# EaglesPU50.net
KiCad netlist of a schematic drawn in Altium Designer
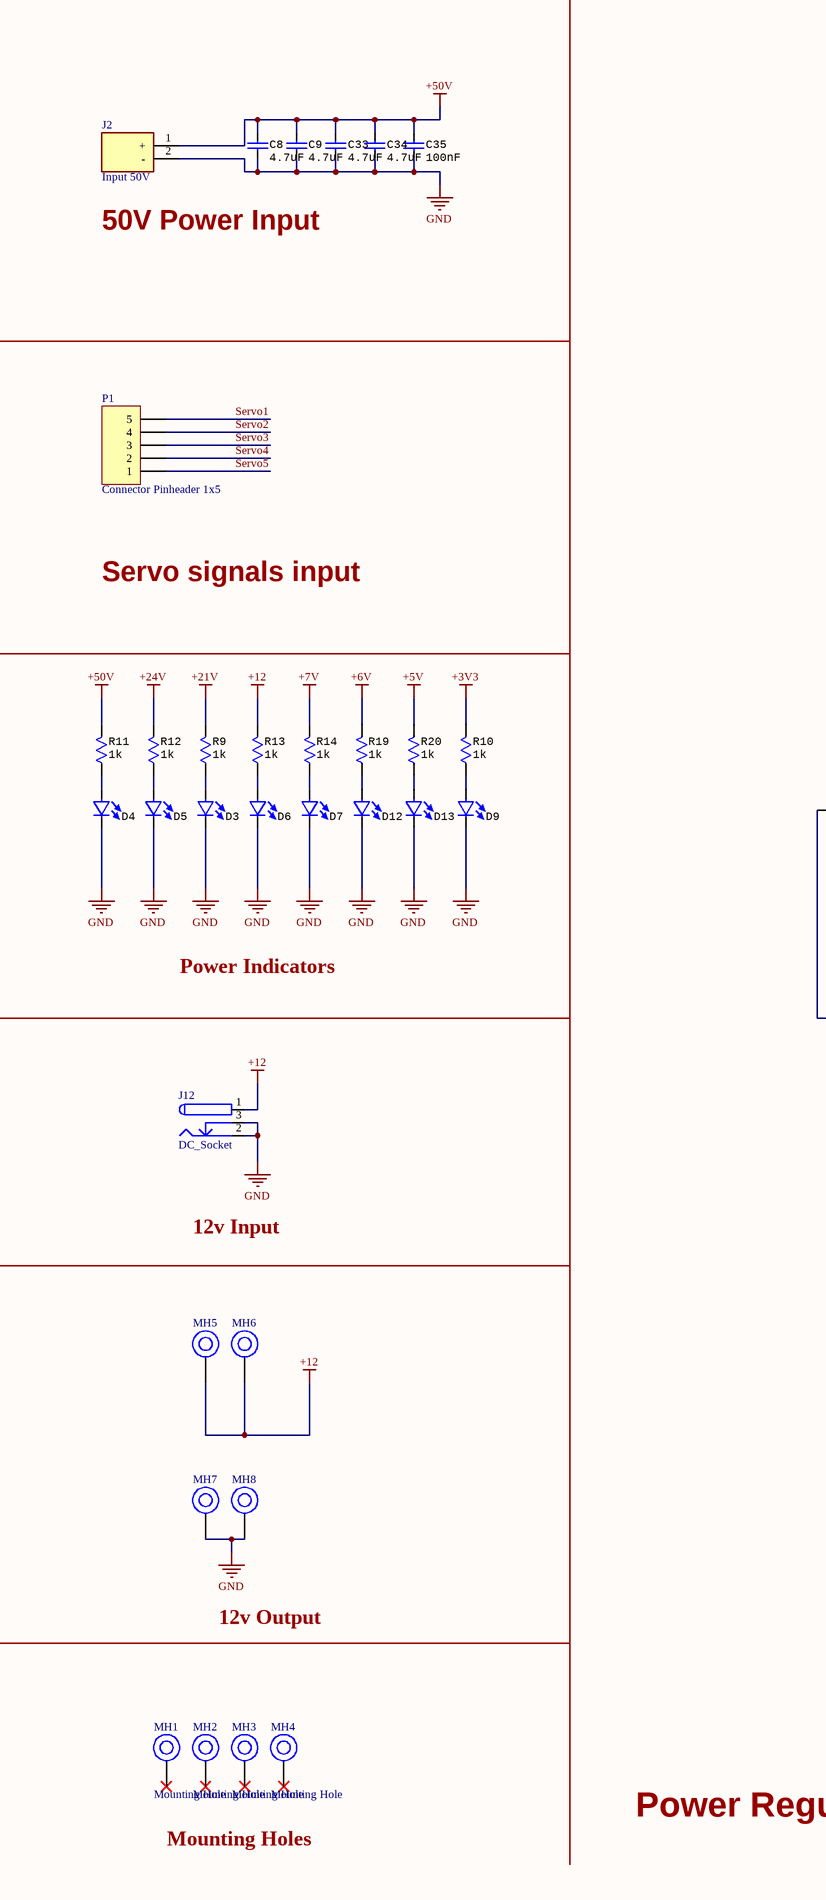
[diagram p0: EaglesPU50.SchDoc, left]
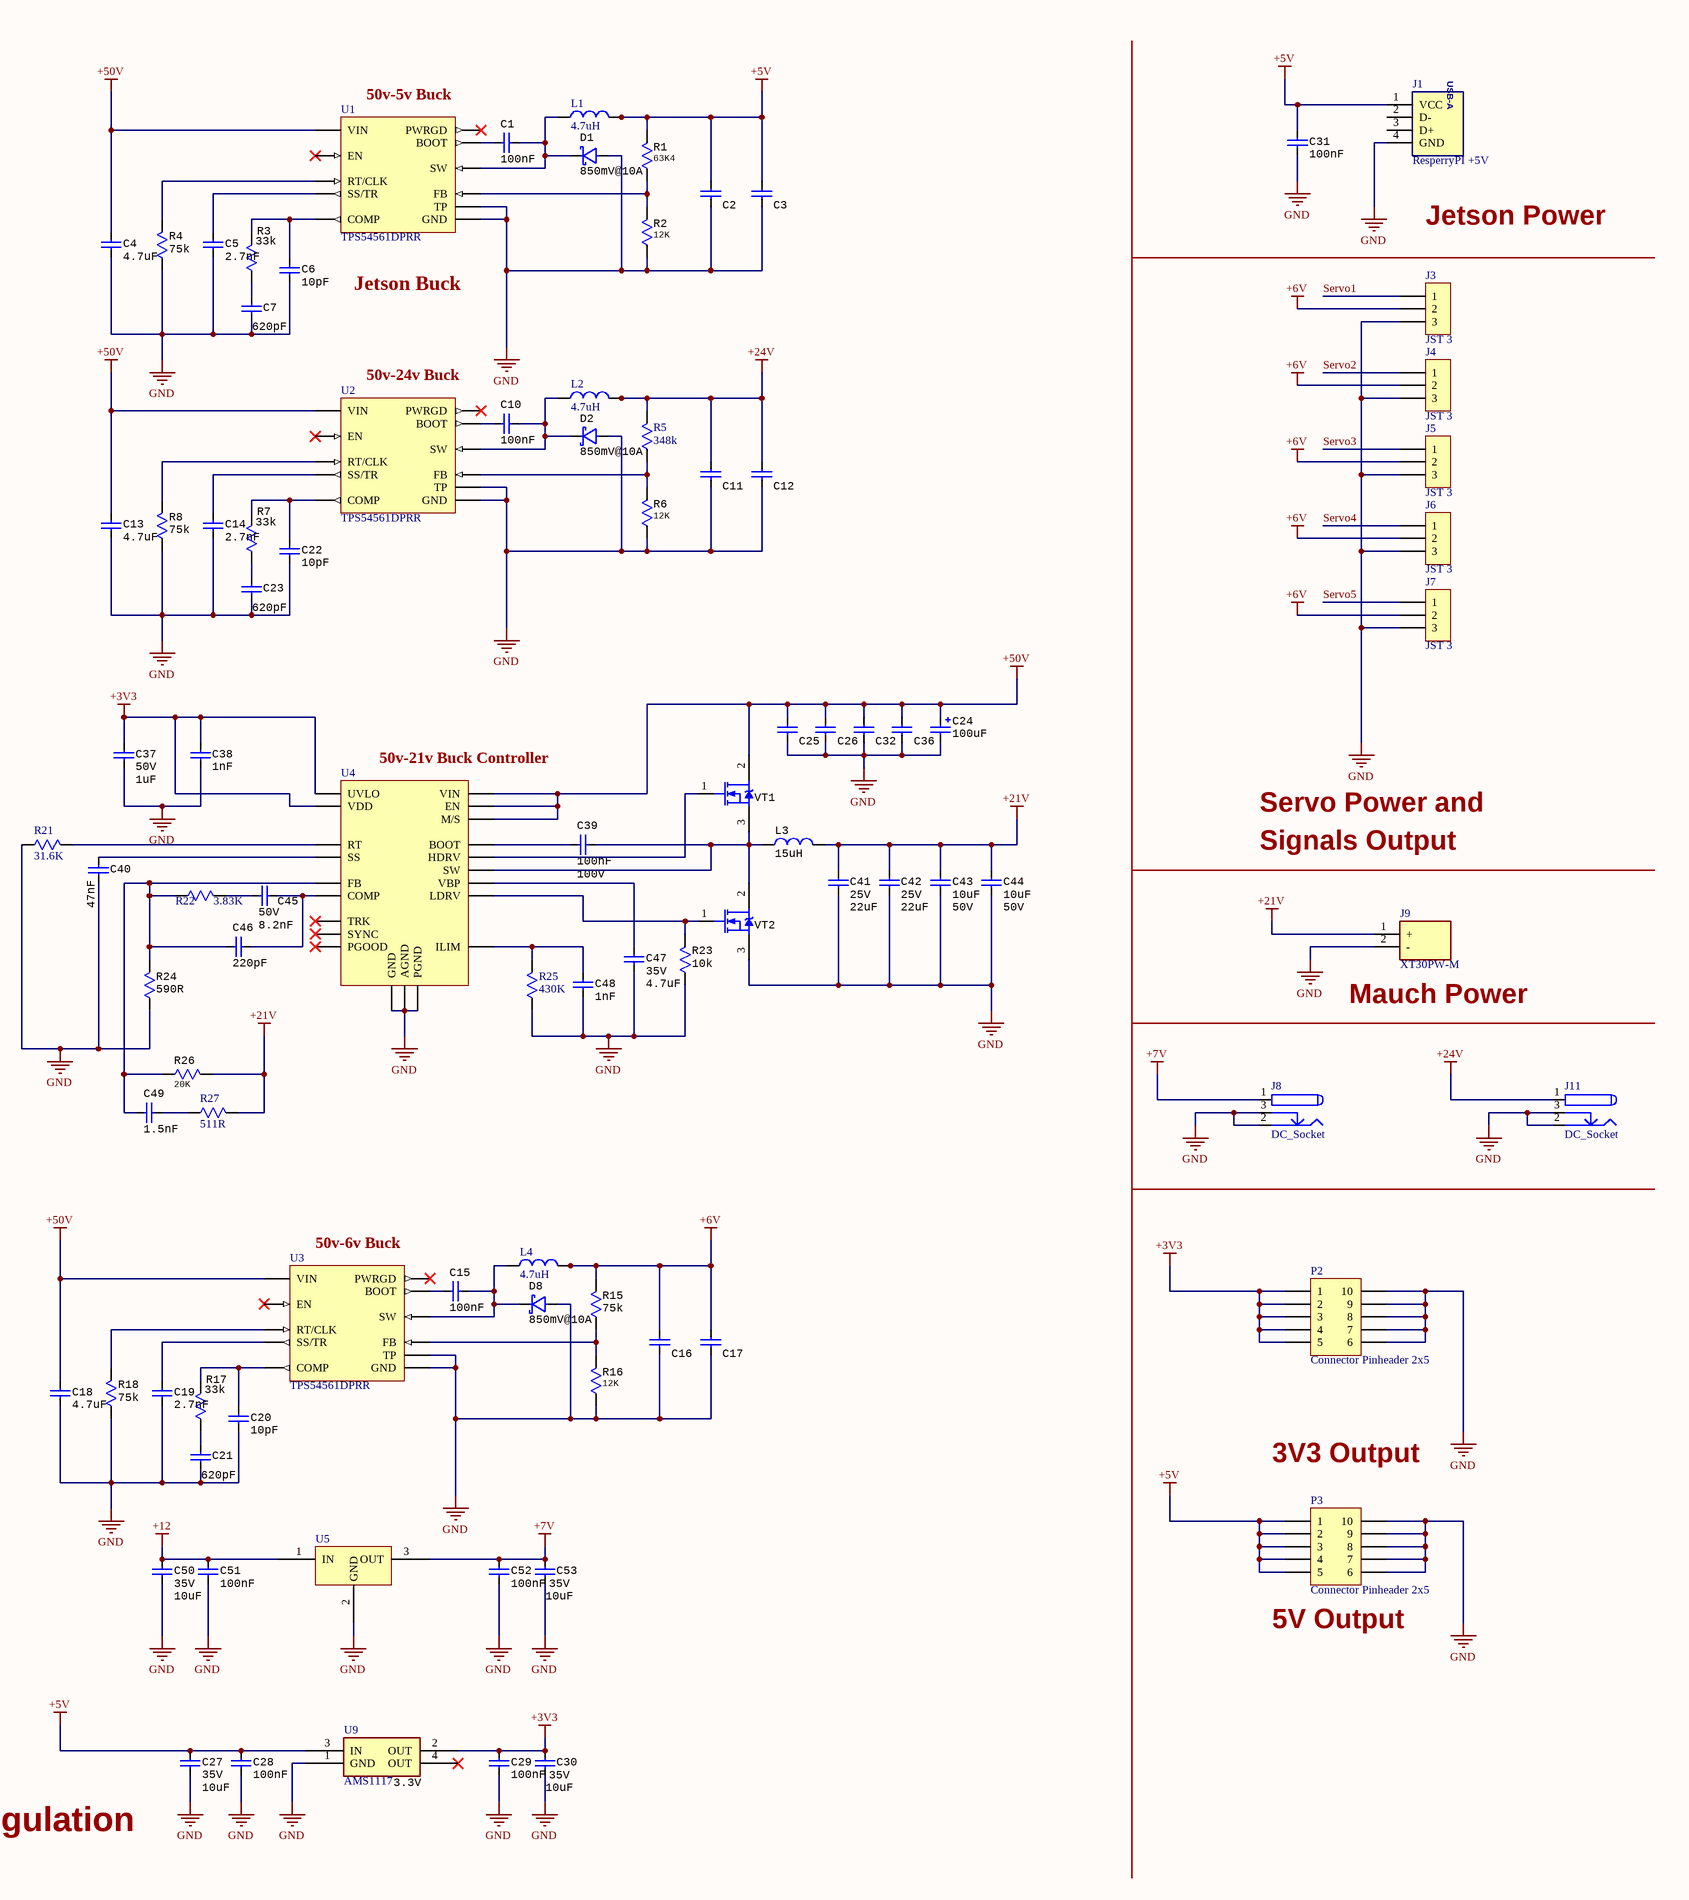
[diagram p1: EaglesPU50.SchDoc, right]

(export (version "E")
  (design (tool "Eeschema 10.0.6"))
  (components
    (comp (ref "C1")
      (value "100nF")
      (footprint "CAP Ceramic SMD 0603")
      (description "0603 0.1 uF 100 V ±10% Tolerance X7R Multilayer Ceramic Capacitor")
      (fields
        (field (name "MANUFACTURER") "Yageo")
        (field (name "MANUFACTURER PART NUMBER") "CC0603KRX7R0BB104")
      )
      (libsource (lib "capacitor") (part "CAP 0603 100nF 100V"))
    )
    (comp (ref "C2")
      (value "~")
      (footprint "CAP Ceramic SMD 1206")
      (description "10V 22uF X7R ±10% 1206 Multilayer Ceramic Capacitors MLCC - SMD/SMT ROHS")
      (fields
        (field (name "MANUFACTURER") "Samsung")
        (field (name "MANUFACTURER PART NUMBER") "GRM31CR61A476ME15L")
      )
      (libsource (lib "capacitor") (part "CAP 1206 47uF 10V X5R"))
    )
    (comp (ref "C3")
      (value "~")
      (footprint "CAP Ceramic SMD 1206")
      (description "10V 22uF X7R ±10% 1206 Multilayer Ceramic Capacitors MLCC - SMD/SMT ROHS")
      (fields
        (field (name "MANUFACTURER") "Samsung")
        (field (name "MANUFACTURER PART NUMBER") "GRM31CR61A476ME15L")
      )
      (libsource (lib "capacitor") (part "CAP 1206 47uF 10V X5R"))
    )
    (comp (ref "C4")
      (value "4.7uF")
      (footprint "CAP Ceramic SMD 1206")
      (description "Cap Ceramic 4.7uF 100V X7S 10% SMD 1206 125°C Emboss T/R")
      (fields
        (field (name "MANUFACTURER PART NUMBER") "GRM31CC72A475KE11L")
        (field (name "MANUFACTURER") "Murata")
      )
      (libsource (lib "Passive") (part "CAP 1206 4.7uF 100V"))
    )
    (comp (ref "C5")
      (value "2.7nF")
      (footprint "CAP Ceramic SMD 0603")
      (description "0603 2.7 nF 50 V ±10 % Tolerance X7R SMT Multilayer Ceramic Capacitor")
      (fields
        (field (name "MANUFACTURER") "Yageo")
        (field (name "MANUFACTURER PART NUMBER") "CC0603KRX7R9BB272")
      )
      (libsource (lib "Passive") (part "CAP 0603 2.7nF 50V"))
    )
    (comp (ref "C6")
      (value "10pF")
      (footprint "CAP Ceramic SMD 0603")
      (description "Surface Mount Ceramic Multilayer Capacitor 10pF 5% C0G 50V 0603 Paper T/R")
      (fields
        (field (name "MANUFACTURER") "Yageo")
        (field (name "MANUFACTURER PART NUMBER") "CC0603JRNPO9BN100")
      )
      (libsource (lib "Passive") (part "CAP 0603 10pF 50V"))
    )
    (comp (ref "C7")
      (value "620pF")
      (footprint "CAP Ceramic SMD 0603")
      (description "Surface Mount Ceramic Multilayer Capacitor 620pF 5% C0G 50V 0603 Paper T/R")
      (fields
        (field (name "MANUFACTURER") "Yageo")
        (field (name "MANUFACTURER PART NUMBER") "CC0603JRNPO9BN621")
      )
      (libsource (lib "Passive") (part "CAP 0603 620pF 50V"))
    )
    (comp (ref "C8")
      (value "4.7uF")
      (footprint "CAP Ceramic SMD 1206")
      (description "Cap Ceramic 4.7uF 100V X7S 10% SMD 1206 125°C Emboss T/R")
      (fields
        (field (name "MANUFACTURER PART NUMBER") "GRM31CC72A475KE11L")
        (field (name "MANUFACTURER") "Murata")
      )
      (libsource (lib "Passive") (part "CAP 1206 4.7uF 100V"))
    )
    (comp (ref "C9")
      (value "4.7uF")
      (footprint "CAP Ceramic SMD 1206")
      (description "Cap Ceramic 4.7uF 100V X7S 10% SMD 1206 125°C Emboss T/R")
      (fields
        (field (name "MANUFACTURER PART NUMBER") "GRM31CC72A475KE11L")
        (field (name "MANUFACTURER") "Murata")
      )
      (libsource (lib "Passive") (part "CAP 1206 4.7uF 100V"))
    )
    (comp (ref "C10")
      (value "100nF")
      (footprint "CAP Ceramic SMD 0603")
      (description "0603 0.1 uF 100 V ±10% Tolerance X7R Multilayer Ceramic Capacitor")
      (fields
        (field (name "MANUFACTURER") "Yageo")
        (field (name "MANUFACTURER PART NUMBER") "CC0603KRX7R0BB104")
      )
      (libsource (lib "capacitor") (part "CAP 0603 100nF 100V"))
    )
    (comp (ref "C11")
      (value "~")
      (footprint "CAP Ceramic SMD 1206")
      (description "10V 22uF X7R ±10% 1206 Multilayer Ceramic Capacitors MLCC - SMD/SMT ROHS")
      (fields
        (field (name "MANUFACTURER") "Samsung")
        (field (name "MANUFACTURER PART NUMBER") "GRM31CR61A476ME15L")
      )
      (libsource (lib "capacitor") (part "CAP 1206 47uF 10V X5R"))
    )
    (comp (ref "C12")
      (value "~")
      (footprint "CAP Ceramic SMD 1206")
      (description "10V 22uF X7R ±10% 1206 Multilayer Ceramic Capacitors MLCC - SMD/SMT ROHS")
      (fields
        (field (name "MANUFACTURER") "Samsung")
        (field (name "MANUFACTURER PART NUMBER") "GRM31CR61A476ME15L")
      )
      (libsource (lib "capacitor") (part "CAP 1206 47uF 10V X5R"))
    )
    (comp (ref "C13")
      (value "4.7uF")
      (footprint "CAP Ceramic SMD 1206")
      (description "Cap Ceramic 4.7uF 100V X7S 10% SMD 1206 125°C Emboss T/R")
      (fields
        (field (name "MANUFACTURER PART NUMBER") "GRM31CC72A475KE11L")
        (field (name "MANUFACTURER") "Murata")
      )
      (libsource (lib "Passive") (part "CAP 1206 4.7uF 100V"))
    )
    (comp (ref "C14")
      (value "2.7nF")
      (footprint "CAP Ceramic SMD 0603")
      (description "0603 2.7 nF 50 V ±10 % Tolerance X7R SMT Multilayer Ceramic Capacitor")
      (fields
        (field (name "MANUFACTURER") "Yageo")
        (field (name "MANUFACTURER PART NUMBER") "CC0603KRX7R9BB272")
      )
      (libsource (lib "Passive") (part "CAP 0603 2.7nF 50V"))
    )
    (comp (ref "C15")
      (value "100nF")
      (footprint "CAP Ceramic SMD 0603")
      (description "0603 0.1 uF 100 V ±10% Tolerance X7R Multilayer Ceramic Capacitor")
      (fields
        (field (name "MANUFACTURER") "Yageo")
        (field (name "MANUFACTURER PART NUMBER") "CC0603KRX7R0BB104")
      )
      (libsource (lib "capacitor") (part "CAP 0603 100nF 100V"))
    )
    (comp (ref "C16")
      (value "~")
      (footprint "CAP Ceramic SMD 1206")
      (description "10V 22uF X7R ±10% 1206 Multilayer Ceramic Capacitors MLCC - SMD/SMT ROHS")
      (fields
        (field (name "MANUFACTURER") "Samsung")
        (field (name "MANUFACTURER PART NUMBER") "GRM31CR61A476ME15L")
      )
      (libsource (lib "capacitor") (part "CAP 1206 47uF 10V X5R"))
    )
    (comp (ref "C17")
      (value "~")
      (footprint "CAP Ceramic SMD 1206")
      (description "10V 22uF X7R ±10% 1206 Multilayer Ceramic Capacitors MLCC - SMD/SMT ROHS")
      (fields
        (field (name "MANUFACTURER") "Samsung")
        (field (name "MANUFACTURER PART NUMBER") "GRM31CR61A476ME15L")
      )
      (libsource (lib "capacitor") (part "CAP 1206 47uF 10V X5R"))
    )
    (comp (ref "C18")
      (value "4.7uF")
      (footprint "CAP Ceramic SMD 1206")
      (description "Cap Ceramic 4.7uF 100V X7S 10% SMD 1206 125°C Emboss T/R")
      (fields
        (field (name "MANUFACTURER PART NUMBER") "GRM31CC72A475KE11L")
        (field (name "MANUFACTURER") "Murata")
      )
      (libsource (lib "Passive") (part "CAP 1206 4.7uF 100V"))
    )
    (comp (ref "C19")
      (value "2.7nF")
      (footprint "CAP Ceramic SMD 0603")
      (description "0603 2.7 nF 50 V ±10 % Tolerance X7R SMT Multilayer Ceramic Capacitor")
      (fields
        (field (name "MANUFACTURER") "Yageo")
        (field (name "MANUFACTURER PART NUMBER") "CC0603KRX7R9BB272")
      )
      (libsource (lib "Passive") (part "CAP 0603 2.7nF 50V"))
    )
    (comp (ref "C20")
      (value "10pF")
      (footprint "CAP Ceramic SMD 0603")
      (description "Surface Mount Ceramic Multilayer Capacitor 10pF 5% C0G 50V 0603 Paper T/R")
      (fields
        (field (name "MANUFACTURER") "Yageo")
        (field (name "MANUFACTURER PART NUMBER") "CC0603JRNPO9BN100")
      )
      (libsource (lib "Passive") (part "CAP 0603 10pF 50V"))
    )
    (comp (ref "C21")
      (value "620pF")
      (footprint "CAP Ceramic SMD 0603")
      (description "Surface Mount Ceramic Multilayer Capacitor 620pF 5% C0G 50V 0603 Paper T/R")
      (fields
        (field (name "MANUFACTURER") "Yageo")
        (field (name "MANUFACTURER PART NUMBER") "CC0603JRNPO9BN621")
      )
      (libsource (lib "Passive") (part "CAP 0603 620pF 50V"))
    )
    (comp (ref "C22")
      (value "10pF")
      (footprint "CAP Ceramic SMD 0603")
      (description "Surface Mount Ceramic Multilayer Capacitor 10pF 5% C0G 50V 0603 Paper T/R")
      (fields
        (field (name "MANUFACTURER") "Yageo")
        (field (name "MANUFACTURER PART NUMBER") "CC0603JRNPO9BN100")
      )
      (libsource (lib "Passive") (part "CAP 0603 10pF 50V"))
    )
    (comp (ref "C23")
      (value "620pF")
      (footprint "CAP Ceramic SMD 0603")
      (description "Surface Mount Ceramic Multilayer Capacitor 620pF 5% C0G 50V 0603 Paper T/R")
      (fields
        (field (name "MANUFACTURER") "Yageo")
        (field (name "MANUFACTURER PART NUMBER") "CC0603JRNPO9BN621")
      )
      (libsource (lib "Passive") (part "CAP 0603 620pF 50V"))
    )
    (comp (ref "C24")
      (value "100uF")
      (footprint "CAP Electrolytic SMD G_10X10.3X10.2(CPOL-EU153CLV-1010)")
      (fields (field (name "MANUFACTURER") "ROQANG") (field (name "MANUFACTURER PART NUMBER") "RT1J101M1010"))
      (libsource (lib "Passive") (part "CAP ELEC 100uF 68V"))
    )
    (comp (ref "C25")
      (value "2.2uF")
      (footprint "CAP Ceramic SMD 1206")
      (description "100V 2.2uF X7R ±10% 1206 Multilayer Ceramic Capacitors MLCC - SMD/SMT ROHS")
      (fields
        (field (name "MANUFACTURER") "Yageo")
        (field (name "MANUFACTURER PART NUMBER") "CC1206KKX7R0BB225")
      )
      (libsource (lib "Passive") (part "CAP 1206 2.2uF 100V"))
    )
    (comp (ref "C26")
      (value "2.2uF")
      (footprint "CAP Ceramic SMD 1206")
      (description "100V 2.2uF X7R ±10% 1206 Multilayer Ceramic Capacitors MLCC - SMD/SMT ROHS")
      (fields
        (field (name "MANUFACTURER") "Yageo")
        (field (name "MANUFACTURER PART NUMBER") "CC1206KKX7R0BB225")
      )
      (libsource (lib "Passive") (part "CAP 1206 2.2uF 100V"))
    )
    (comp (ref "C27")
      (value "10uF")
      (footprint "CAP Ceramic SMD 0603")
      (description "Cap Ceramic 10uF 35V X5R 20% Pad SMD 0603 85C T/R")
      (fields
        (field (name "MANUFACTURER") "Murata")
        (field (name "MANUFACTURER PART NUMBER") "GRM188R6YA106MA73D")
        (field (name "VOLTAGE") "35V")
      )
      (libsource (lib "Passive") (part "CAP 0603 10uF 35V"))
    )
    (comp (ref "C28")
      (value "100nF")
      (footprint "CAP Ceramic SMD 0603")
      (description "0603 0.1 uF 100 V ±10% Tolerance X7R Multilayer Ceramic Capacitor")
      (fields
        (field (name "MANUFACTURER") "Yageo")
        (field (name "MANUFACTURER PART NUMBER") "AC0603KRX7R0BB104")
      )
      (libsource (lib "capacitor") (part "CAP 0603 100nF 100V"))
    )
    (comp (ref "C29")
      (value "100nF")
      (footprint "CAP Ceramic SMD 0603")
      (description "0603 0.1 uF 100 V ±10% Tolerance X7R Multilayer Ceramic Capacitor")
      (fields
        (field (name "MANUFACTURER") "Yageo")
        (field (name "MANUFACTURER PART NUMBER") "AC0603KRX7R0BB104")
      )
      (libsource (lib "capacitor") (part "CAP 0603 100nF 100V"))
    )
    (comp (ref "C30")
      (value "10uF")
      (footprint "CAP Ceramic SMD 0603")
      (description "Cap Ceramic 10uF 35V X5R 20% Pad SMD 0603 85C T/R")
      (fields
        (field (name "MANUFACTURER") "Murata")
        (field (name "MANUFACTURER PART NUMBER") "GRM188R6YA106MA73D")
        (field (name "VOLTAGE") "35V")
      )
      (libsource (lib "Passive") (part "CAP 0603 10uF 35V"))
    )
    (comp (ref "C31")
      (value "100nF")
      (footprint "CAP Ceramic SMD 0603")
      (description "0603 0.1 uF 100 V ±10% Tolerance X7R Multilayer Ceramic Capacitor")
      (fields
        (field (name "MANUFACTURER") "Yageo")
        (field (name "MANUFACTURER PART NUMBER") "CC0603KRX7R0BB104")
      )
      (libsource (lib "capacitor") (part "CAP 0603 100nF 100V"))
    )
    (comp (ref "C32")
      (value "2.2uF")
      (footprint "CAP Ceramic SMD 1206")
      (description "100V 2.2uF X7R ±10% 1206 Multilayer Ceramic Capacitors MLCC - SMD/SMT ROHS")
      (fields
        (field (name "MANUFACTURER") "Yageo")
        (field (name "MANUFACTURER PART NUMBER") "CC1206KKX7R0BB225")
      )
      (libsource (lib "Passive") (part "CAP 1206 2.2uF 100V"))
    )
    (comp (ref "C33")
      (value "4.7uF")
      (footprint "CAP Ceramic SMD 1206")
      (description "Cap Ceramic 4.7uF 100V X7S 10% SMD 1206 125°C Emboss T/R")
      (fields
        (field (name "MANUFACTURER PART NUMBER") "GRM31CC72A475KE11L")
        (field (name "MANUFACTURER") "Murata")
      )
      (libsource (lib "Passive") (part "CAP 1206 4.7uF 100V"))
    )
    (comp (ref "C34")
      (value "4.7uF")
      (footprint "CAP Ceramic SMD 1206")
      (description "Cap Ceramic 4.7uF 100V X7S 10% SMD 1206 125°C Emboss T/R")
      (fields
        (field (name "MANUFACTURER PART NUMBER") "GRM31CC72A475KE11L")
        (field (name "MANUFACTURER") "Murata")
      )
      (libsource (lib "Passive") (part "CAP 1206 4.7uF 100V"))
    )
    (comp (ref "C35")
      (value "100nF")
      (footprint "CAP Ceramic SMD 0603")
      (description "0603 0.1 uF 100 V ±10% Tolerance X7R Multilayer Ceramic Capacitor")
      (fields
        (field (name "MANUFACTURER") "Yageo")
        (field (name "MANUFACTURER PART NUMBER") "CC0603KRX7R0BB104")
      )
      (libsource (lib "capacitor") (part "CAP 0603 100nF 100V"))
    )
    (comp (ref "C36")
      (value "2.2uF")
      (footprint "CAP Ceramic SMD 1206")
      (description "100V 2.2uF X7R ±10% 1206 Multilayer Ceramic Capacitors MLCC - SMD/SMT ROHS")
      (fields
        (field (name "MANUFACTURER") "Yageo")
        (field (name "MANUFACTURER PART NUMBER") "CC1206KKX7R0BB225")
      )
      (libsource (lib "Passive") (part "CAP 1206 2.2uF 100V"))
    )
    (comp (ref "C37")
      (value "1uF")
      (footprint "CAP Ceramic SMD 0603")
      (description "50V 1uF X7R ±10% 0603 Multilayer Ceramic Capacitors MLCC - SMD/SMT ROHS")
      (fields
        (field (name "MANUFACTURER") "YAGEO")
        (field (name "MANUFACTURER PART NUMBER") "CC0603KRX7R9BB105")
        (field (name "VOLTAGE") "50V")
      )
      (libsource (lib "Passive") (part "CAP 0603 1uF 50V X7R 10%"))
    )
    (comp (ref "C38")
      (value "1nF")
      (footprint "CAP Ceramic SMD 0603")
      (description "CAP CER 1100PF 50V C0G/NP0 0603")
      (fields
        (field (name "MANUFACTURER") "YAGEO")
        (field (name "MANUFACTURER PART NUMBER") "CC0603KRX7R9BB102")
      )
      (libsource (lib "Passive") (part "CAP 0603 1nF 50V"))
    )
    (comp (ref "C39")
      (value "100nF")
      (footprint "CAP Ceramic SMD 0603")
      (description "100V 100nF X7R ±10% 0603 Multilayer Ceramic Capacitors MLCC - SMD/SMT ROHS")
      (fields
        (field (name "MANUFACTURER") "Yageo")
        (field (name "MANUFACTURER PART NUMBER") "CC0603KRX7R0BB104")
        (field (name "VOLTAGE") "100V")
      )
      (libsource (lib "Passive") (part "CAP 0603 100nF 100V X7R 10%"))
    )
    (comp (ref "C40")
      (value "47nF")
      (footprint "CAP Ceramic SMD 0603")
      (description "50V 47nF X7R ±10% 0603 Multilayer Ceramic Capacitors MLCC - SMD/SMT ROHS")
      (fields
        (field (name "MANUFACTURER") "Yageo")
        (field (name "MANUFACTURER PART NUMBER") "CC0603KRX7R9BB473")
      )
      (libsource (lib "Passive") (part "CAP 0603 47nF 50V"))
    )
    (comp (ref "C41")
      (value "22uF")
      (footprint "CAP Ceramic SMD 0805")
      (description "25V 22uF X5R ±20% 0805 Multilayer Ceramic Capacitors MLCC")
      (fields
        (field (name "MANUFACTURER") "YAGEO")
        (field (name "MANUFACTURER PART NUMBER") "CC0805MKX5R8BB226")
        (field (name "VOLTAGE") "25V")
      )
      (libsource (lib "Passive") (part "CAP 0805 22uF 25V"))
    )
    (comp (ref "C42")
      (value "22uF")
      (footprint "CAP Ceramic SMD 0805")
      (description "25V 22uF X5R ±20% 0805 Multilayer Ceramic Capacitors MLCC")
      (fields
        (field (name "MANUFACTURER") "YAGEO")
        (field (name "MANUFACTURER PART NUMBER") "CC0805MKX5R8BB226")
        (field (name "VOLTAGE") "25V")
      )
      (libsource (lib "Passive") (part "CAP 0805 22uF 25V"))
    )
    (comp (ref "C43")
      (value "10uF")
      (footprint "CAP Ceramic SMD 1206")
      (description "50V 10uF X5R ±10% 1206 Multilayer Ceramic Capacitors MLCC - SMD/SMT ROHS")
      (fields
        (field (name "MANUFACTURER") "Samsung")
        (field (name "MANUFACTURER PART NUMBER") "CL31A106KBHNNNE")
        (field (name "VOLTAGE") "50V")
      )
      (libsource (lib "Passive") (part "CAP 1206 10uF 50V X5R 10%"))
    )
    (comp (ref "C44")
      (value "10uF")
      (footprint "CAP Ceramic SMD 1206")
      (description "50V 10uF X5R ±10% 1206 Multilayer Ceramic Capacitors MLCC - SMD/SMT ROHS")
      (fields
        (field (name "MANUFACTURER") "Samsung")
        (field (name "MANUFACTURER PART NUMBER") "CL31A106KBHNNNE")
        (field (name "VOLTAGE") "50V")
      )
      (libsource (lib "Passive") (part "CAP 1206 10uF 50V X5R 10%"))
    )
    (comp (ref "C45")
      (value "8.2nF")
      (footprint "CAP Ceramic SMD 0603")
      (description "50V 8.2nF X7R ±10% 0603 Multilayer Ceramic Capacitors MLCC - SMD/SMT ROHS")
      (fields
        (field (name "MANUFACTURER") "YAGEO")
        (field (name "MANUFACTURER PART NUMBER") "CC0603KRX7R9BB822")
        (field (name "VOLTAGE") "50V")
        (field (name "CAPACITANCE") "8.2nF")
      )
      (libsource (lib "Passive") (part "CAP 0603 8.2nF 50V"))
    )
    (comp (ref "C46")
      (value "220pF")
      (footprint "CAP Ceramic SMD 0603")
      (description "50V 220pF X7R ±10% 0603 Multilayer Ceramic Capacitors MLCC - SMD/SMT ROHS")
      (fields
        (field (name "MANUFACTURER") "Yageo")
        (field (name "MANUFACTURER PART NUMBER") "CC0603KRX7R9BB221")
      )
      (libsource (lib "Passive") (part "CAP 0603 220pF 50V"))
    )
    (comp (ref "C47")
      (value "4.7uF")
      (footprint "CAP Ceramic SMD 0603")
      (description "25V 4.7uF X5R ±10% 0603 Multilayer Ceramic Capacitors MLCC - SMD/SMT ROHS")
      (fields
        (field (name "MANUFACTURER") "Samsung Electro-Mechanics")
        (field (name "MANUFACTURER PART NUMBER") "CL10A475KA8NQNC")
        (field (name "VOLTAGE") "35V")
      )
      (libsource (lib "Passive") (part "CAP 0603 4.7uF 25V X5R 10%"))
    )
    (comp (ref "C48")
      (value "1nF")
      (footprint "CAP Ceramic SMD 0603")
      (description "CAP CER 1100PF 50V C0G/NP0 0603")
      (fields
        (field (name "MANUFACTURER") "YAGEO")
        (field (name "MANUFACTURER PART NUMBER") "CC0603KRX7R9BB102")
      )
      (libsource (lib "Passive") (part "CAP 0603 1nF 50V"))
    )
    (comp (ref "C49")
      (value "1.5nF")
      (footprint "CAP Ceramic SMD 0603")
      (description "50V 1.5nF X7R ±10% 0603 Multilayer Ceramic Capacitors MLCC - SMD/SMT ROHS")
      (fields
        (field (name "MANUFACTURER") "Yageo")
        (field (name "MANUFACTURER PART NUMBER") "CC0603KRX7R9BB152")
      )
      (libsource (lib "Passive") (part "CAP 0603 1.5nF 50V"))
    )
    (comp (ref "C50")
      (value "10uF")
      (footprint "CAP Ceramic SMD 0603")
      (description "Cap Ceramic 10uF 35V X5R 20% Pad SMD 0603 85C T/R")
      (fields
        (field (name "MANUFACTURER") "Murata")
        (field (name "MANUFACTURER PART NUMBER") "GRM188R6YA106MA73D")
        (field (name "VOLTAGE") "35V")
      )
      (libsource (lib "Passive") (part "CAP 0603 10uF 35V"))
    )
    (comp (ref "C51")
      (value "100nF")
      (footprint "CAP Ceramic SMD 0603")
      (description "0603 0.1 uF 100 V ±10% Tolerance X7R Multilayer Ceramic Capacitor")
      (fields
        (field (name "MANUFACTURER") "Yageo")
        (field (name "MANUFACTURER PART NUMBER") "AC0603KRX7R0BB104")
      )
      (libsource (lib "capacitor") (part "CAP 0603 100nF 100V"))
    )
    (comp (ref "C52")
      (value "100nF")
      (footprint "CAP Ceramic SMD 0603")
      (description "0603 0.1 uF 100 V ±10% Tolerance X7R Multilayer Ceramic Capacitor")
      (fields
        (field (name "MANUFACTURER") "Yageo")
        (field (name "MANUFACTURER PART NUMBER") "AC0603KRX7R0BB104")
      )
      (libsource (lib "capacitor") (part "CAP 0603 100nF 100V"))
    )
    (comp (ref "C53")
      (value "10uF")
      (footprint "CAP Ceramic SMD 0603")
      (description "Cap Ceramic 10uF 35V X5R 20% Pad SMD 0603 85C T/R")
      (fields
        (field (name "MANUFACTURER") "Murata")
        (field (name "MANUFACTURER PART NUMBER") "GRM188R6YA106MA73D")
        (field (name "VOLTAGE") "35V")
      )
      (libsource (lib "Passive") (part "CAP 0603 10uF 35V"))
    )
    (comp (ref "D1")
      (value "850mV@10A")
      (footprint "TO-277")
      (description "100V 750mV@10A 10A TO-277 Schottky Barrier Diodes (SBD) ROHS")
      (fields
        (field (name "MANUFACTURER") "MDD（Microdiode Electronics）")
        (field (name "MANUFACTURER PART NUMBER") "SB10100L")
      )
      (libsource (lib "Diode") (part "Schottky 100V 750mV@10A"))
    )
    (comp (ref "D2")
      (value "850mV@10A")
      (footprint "TO-277")
      (description "100V 750mV@10A 10A TO-277 Schottky Barrier Diodes (SBD) ROHS")
      (fields
        (field (name "MANUFACTURER") "MDD（Microdiode Electronics）")
        (field (name "MANUFACTURER PART NUMBER") "SB10100L")
      )
      (libsource (lib "Diode") (part "Schottky 100V 750mV@10A"))
    )
    (comp (ref "D3")
      (value "~")
      (footprint "LED SMD 0805G")
      (description "emerald 0805 Light Emitting Diodes (LED) ROHS")
      (fields
        (field (name "MANUFACTURER") "FOSHAN Nationstar Optoelectronics")
        (field (name "MANUFACTURER PART NUMBER") "NCD0805G1")
      )
      (libsource (lib "diode") (part "LED 0805 Emerald"))
    )
    (comp (ref "D4")
      (value "~")
      (footprint "LED SMD 0805G")
      (description "emerald 0805 Light Emitting Diodes (LED) ROHS")
      (fields
        (field (name "MANUFACTURER") "FOSHAN Nationstar Optoelectronics")
        (field (name "MANUFACTURER PART NUMBER") "NCD0805G1")
      )
      (libsource (lib "diode") (part "LED 0805 Emerald"))
    )
    (comp (ref "D5")
      (value "~")
      (footprint "LED SMD 0805G")
      (description "emerald 0805 Light Emitting Diodes (LED) ROHS")
      (fields
        (field (name "MANUFACTURER") "FOSHAN Nationstar Optoelectronics")
        (field (name "MANUFACTURER PART NUMBER") "NCD0805G1")
      )
      (libsource (lib "diode") (part "LED 0805 Emerald"))
    )
    (comp (ref "D6")
      (value "~")
      (footprint "LED SMD 0805G")
      (description "emerald 0805 Light Emitting Diodes (LED) ROHS")
      (fields
        (field (name "MANUFACTURER") "FOSHAN Nationstar Optoelectronics")
        (field (name "MANUFACTURER PART NUMBER") "NCD0805G1")
      )
      (libsource (lib "diode") (part "LED 0805 Emerald"))
    )
    (comp (ref "D7")
      (value "~")
      (footprint "LED SMD 0805G")
      (description "emerald 0805 Light Emitting Diodes (LED) ROHS")
      (fields
        (field (name "MANUFACTURER") "FOSHAN Nationstar Optoelectronics")
        (field (name "MANUFACTURER PART NUMBER") "NCD0805G1")
      )
      (libsource (lib "diode") (part "LED 0805 Emerald"))
    )
    (comp (ref "D8")
      (value "850mV@10A")
      (footprint "TO-277")
      (description "100V 750mV@10A 10A TO-277 Schottky Barrier Diodes (SBD) ROHS")
      (fields
        (field (name "MANUFACTURER") "MDD（Microdiode Electronics）")
        (field (name "MANUFACTURER PART NUMBER") "SB10100L")
      )
      (libsource (lib "Diode") (part "Schottky 100V 750mV@10A"))
    )
    (comp (ref "D9")
      (value "~")
      (footprint "LED SMD 0805G")
      (description "emerald 0805 Light Emitting Diodes (LED) ROHS")
      (fields
        (field (name "MANUFACTURER") "FOSHAN Nationstar Optoelectronics")
        (field (name "MANUFACTURER PART NUMBER") "NCD0805G1")
      )
      (libsource (lib "diode") (part "LED 0805 Emerald"))
    )
    (comp (ref "D12")
      (value "~")
      (footprint "LED SMD 0805G")
      (description "emerald 0805 Light Emitting Diodes (LED) ROHS")
      (fields
        (field (name "MANUFACTURER") "FOSHAN Nationstar Optoelectronics")
        (field (name "MANUFACTURER PART NUMBER") "NCD0805G1")
      )
      (libsource (lib "diode") (part "LED 0805 Emerald"))
    )
    (comp (ref "D13")
      (value "~")
      (footprint "LED SMD 0805G")
      (description "emerald 0805 Light Emitting Diodes (LED) ROHS")
      (fields
        (field (name "MANUFACTURER") "FOSHAN Nationstar Optoelectronics")
        (field (name "MANUFACTURER PART NUMBER") "NCD0805G1")
      )
      (libsource (lib "diode") (part "LED 0805 Emerald"))
    )
    (comp (ref "J1")
      (value "ResperryPI +5V")
      (footprint "USB-A/S_A")
      (libsource (lib "USB connectors") (part "Connector_USB-A"))
    )
    (comp (ref "J2")
      (value "Input 50V")
      (footprint "XT60PW-M")
      (description "Power Connectors ROHS")
      (fields
        (field (name "MANUFACTURER") "Changzhou Amass Elec")
        (field (name "MANUFACTURERPARTNUMBER") "XT60PW-M")
      )
      (libsource (lib "Power connectors") (part "XT60PW-M"))
    )
    (comp (ref "J3")
      (value "JST 3")
      (footprint "VH3.96-3AW")
      (description "MaleHeader 3x1")
      (libsource (lib "Signal connectors") (part "JST 3"))
    )
    (comp (ref "J4")
      (value "JST 3")
      (footprint "VH3.96-3AW")
      (description "MaleHeader 3x1")
      (libsource (lib "Signal connectors") (part "JST 3"))
    )
    (comp (ref "J5")
      (value "JST 3")
      (footprint "VH3.96-3AW")
      (description "MaleHeader 3x1")
      (libsource (lib "Signal connectors") (part "JST 3"))
    )
    (comp (ref "J6")
      (value "JST 3")
      (footprint "VH3.96-3AW")
      (description "MaleHeader 3x1")
      (libsource (lib "Signal connectors") (part "JST 3"))
    )
    (comp (ref "J7")
      (value "JST 3")
      (footprint "VH3.96-3AW")
      (description "MaleHeader 3x1")
      (libsource (lib "Signal connectors") (part "JST 3"))
    )
    (comp (ref "J8")
      (value "DC_Socket")
      (footprint "DC-002")
      (description "CIRCULAR DC POWER CONNECTOR\r\nRated Current: 7.5A\r\nRated Volatage: 20VDC")
      (libsource (lib "Power connectors") (part "DC_Socket"))
    )
    (comp (ref "J9")
      (value "XT30PW-M")
      (footprint "AMASS_XT30PW-F")
      (description "Power Connectors ROHS")
      (fields (field (name "MANUFACTURER") "Changzhou Amass Elec"))
      (libsource (lib "Power connectors") (part "XT30PW-M"))
    )
    (comp (ref "J11")
      (value "DC_Socket")
      (footprint "DC-002")
      (description "CIRCULAR DC POWER CONNECTOR\r\nRated Current: 7.5A\r\nRated Volatage: 20VDC")
      (libsource (lib "Power connectors") (part "DC_Socket"))
    )
    (comp (ref "J12")
      (value "DC_Socket")
      (footprint "DC-002")
      (description "CIRCULAR DC POWER CONNECTOR\r\nRated Current: 7.5A\r\nRated Volatage: 20VDC")
      (libsource (lib "") (part "DC_Socket_1"))
    )
    (comp (ref "L1")
      (value "4.7uH")
      (footprint "XLS1040")
      (description "9A 4.7uH ±20% 17mΩ 15A SMD,11.5x10x3.8mm Power Inductors ROHS")
      (fields
        (field (name "MANUFACTURER") "Cjiang")
        (field (name "MANUFACTURER PART NUMBER") "FXL1040-4R7-M")
      )
      (libsource (lib "Passive") (part "IND 0403 4.7uH 20%"))
    )
    (comp (ref "L2")
      (value "4.7uH")
      (footprint "XLS1040")
      (description "9A 4.7uH ±20% 17mΩ 15A SMD,11.5x10x3.8mm Power Inductors ROHS")
      (fields
        (field (name "MANUFACTURER") "Cjiang")
        (field (name "MANUFACTURER PART NUMBER") "FXL1040-4R7-M")
      )
      (libsource (lib "Passive") (part "IND 0403 4.7uH 20%"))
    )
    (comp (ref "L3")
      (value "15uH")
      (footprint "MDA1365-150M")
      (description "11A 15uH ±20% 13.5A 22mΩ SMD,12.6x13.5mm Inductors (SMD) ROHS")
      (fields
        (field (name "MANUFACTURER") "KOHERelec")
        (field (name "MANUFACTURER PART NUMBER") "MDA1365-150M")
      )
      (libsource (lib "Passive") (part "MDA1365-150M"))
    )
    (comp (ref "L4")
      (value "4.7uH")
      (footprint "XLS1040")
      (description "9A 4.7uH ±20% 17mΩ 15A SMD,11.5x10x3.8mm Power Inductors ROHS")
      (fields
        (field (name "MANUFACTURER") "Cjiang")
        (field (name "MANUFACTURER PART NUMBER") "FXL1040-4R7-M")
      )
      (libsource (lib "Passive") (part "IND 0403 4.7uH 20%"))
    )
    (comp (ref "MH1")
      (value "Mounting Hole")
      (footprint "Connector Mounting hole TH 3mm")
      (libsource (lib "Bypass, Testpoint and Holes") (part "Mounting Hole"))
    )
    (comp (ref "MH2")
      (value "Mounting Hole")
      (footprint "Connector Mounting hole TH 3mm")
      (libsource (lib "Bypass, Testpoint and Holes") (part "Mounting Hole"))
    )
    (comp (ref "MH3")
      (value "Mounting Hole")
      (footprint "Connector Mounting hole TH 3mm")
      (libsource (lib "Bypass, Testpoint and Holes") (part "Mounting Hole"))
    )
    (comp (ref "MH4")
      (value "Mounting Hole")
      (footprint "Connector Mounting hole TH 3mm")
      (libsource (lib "Bypass, Testpoint and Holes") (part "Mounting Hole"))
    )
    (comp (ref "MH5")
      (value "Mounting Hole")
      (footprint "Connector Mounting hole TH 1mm SOLID")
      (libsource (lib "Bypass, Testpoint and Holes") (part "Mounting Hole"))
    )
    (comp (ref "MH6")
      (value "Mounting Hole")
      (footprint "Connector Mounting hole TH 1mm SOLID")
      (libsource (lib "Bypass, Testpoint and Holes") (part "Mounting Hole"))
    )
    (comp (ref "MH7")
      (value "Mounting Hole")
      (footprint "Connector Mounting hole TH 1mm SOLID")
      (libsource (lib "Bypass, Testpoint and Holes") (part "Mounting Hole"))
    )
    (comp (ref "MH8")
      (value "Mounting Hole")
      (footprint "Connector Mounting hole TH 1mm SOLID")
      (libsource (lib "Bypass, Testpoint and Holes") (part "Mounting Hole"))
    )
    (comp (ref "P1")
      (value "Connector Pinheader 1x5")
      (footprint "Header 2.54X5")
      (description "Header_5x1")
      (libsource (lib "Signal connectors") (part "Connector Pinheader 1x5"))
    )
    (comp (ref "P2")
      (value "Connector Pinheader 2x5")
      (footprint "Header 2.54_2X5")
      (description "Header_2X5")
      (libsource (lib "Signal connectors") (part "Connector Pinheader 2x5"))
    )
    (comp (ref "P3")
      (value "Connector Pinheader 2x5")
      (footprint "Header 2.54_2X5")
      (description "Header_2X5")
      (libsource (lib "Signal connectors") (part "Connector Pinheader 2x5"))
    )
    (comp (ref "R1")
      (value "63K4")
      (footprint "RES SMD 0603")
      (fields
        (field (name "MANUFACTURER") "Yageo")
        (field (name "MANUFACTURER PART NUMBER") "AC0603FR-0763K4L")
        (field (name "TOLERANCE") "1%")
      )
      (libsource (lib "Passive") (part "RES 0603 63K4 1%"))
    )
    (comp (ref "R2")
      (value "12K")
      (footprint "RES SMD 0603")
      (fields
        (field (name "MANUFACTURER") "Yageo")
        (field (name "MANUFACTURER PART NUMBER") "RC0603FR-0712KL")
        (field (name "TOLERANCE") "1%")
      )
      (libsource (lib "Passive") (part "RES 0603 12K 1%"))
    )
    (comp (ref "R3")
      (value "33k")
      (footprint "RES SMD 0603")
      (fields
        (field (name "MANUFACTURER") "Uniroyal")
        (field (name "MANUFACTURER PART NUMBER") "0603WAF3902T5E")
      )
      (libsource (lib "Passive") (part "RES 0603 39k 1%"))
    )
    (comp (ref "R4")
      (value "75k")
      (footprint "RES SMD 0603")
      (description "Res Thick Film 0603 75K Ohm 1% 0.1W(1/10W) ±100ppm/C Pad SMD Automotive T/R")
      (fields
        (field (name "MANUFACTURER") "Panasonic")
        (field (name "MANUFACTURER PART NUMBER") "ERJ3RBD7502V")
      )
      (libsource (lib "Passive") (part "RES 0603 75k 1%"))
    )
    (comp (ref "R5")
      (value "348k")
      (footprint "RES SMD 0805")
      (description "125mW Thick Film Resistors ±100ppm/℃ ±1% 348kΩ 0805 Chip Resistor - Surface Mount ROHS")
      (fields
        (field (name "MANUFACTURER") "PANASONIC")
        (field (name "MANUFACTURER PART NUMBER") "ERJ6ENF3483V")
        (field (name "RESISTANCE") "348k")
      )
      (libsource (lib "Passive") (part "RES 0805 348k 1%"))
    )
    (comp (ref "R6")
      (value "12K")
      (footprint "RES SMD 0603")
      (fields
        (field (name "MANUFACTURER") "Yageo")
        (field (name "MANUFACTURER PART NUMBER") "RC0603FR-0712KL")
        (field (name "TOLERANCE") "1%")
      )
      (libsource (lib "Passive") (part "RES 0603 12K 1%"))
    )
    (comp (ref "R7")
      (value "33k")
      (footprint "RES SMD 0603")
      (fields
        (field (name "MANUFACTURER") "Uniroyal")
        (field (name "MANUFACTURER PART NUMBER") "0603WAF3902T5E")
      )
      (libsource (lib "Passive") (part "RES 0603 39k 1%"))
    )
    (comp (ref "R8")
      (value "75k")
      (footprint "RES SMD 0603")
      (description "Res Thick Film 0603 75K Ohm 1% 0.1W(1/10W) ±100ppm/C Pad SMD Automotive T/R")
      (fields
        (field (name "MANUFACTURER") "Panasonic")
        (field (name "MANUFACTURER PART NUMBER") "ERJ3RBD7502V")
      )
      (libsource (lib "Passive") (part "RES 0603 75k 1%"))
    )
    (comp (ref "R9")
      (value "1k")
      (footprint "RES SMD 0603")
      (description "Res Thick Film 0603 1K Ohm 1% 1/10W ±100ppm/°C Molded SMD Punched Carrier T/R")
      (fields
        (field (name "MANUFACTURER") "Panasonic")
        (field (name "MANUFACTURER PART NUMBER") "ERJ3EKF1001V")
      )
      (libsource (lib "Passive") (part "RES 0603 1k 1%"))
    )
    (comp (ref "R10")
      (value "1k")
      (footprint "RES SMD 0603")
      (description "Res Thick Film 0603 1K Ohm 1% 1/10W ±100ppm/°C Molded SMD Punched Carrier T/R")
      (fields
        (field (name "MANUFACTURER") "Panasonic")
        (field (name "MANUFACTURER PART NUMBER") "ERJ3EKF1001V")
      )
      (libsource (lib "Passive") (part "RES 0603 1k 1%"))
    )
    (comp (ref "R11")
      (value "1k")
      (footprint "RES SMD 0603")
      (description "Res Thick Film 0603 1K Ohm 1% 1/10W ±100ppm/°C Molded SMD Punched Carrier T/R")
      (fields
        (field (name "MANUFACTURER") "Panasonic")
        (field (name "MANUFACTURER PART NUMBER") "ERJ3EKF1001V")
      )
      (libsource (lib "Passive") (part "RES 0603 1k 1%"))
    )
    (comp (ref "R12")
      (value "1k")
      (footprint "RES SMD 0603")
      (description "Res Thick Film 0603 1K Ohm 1% 1/10W ±100ppm/°C Molded SMD Punched Carrier T/R")
      (fields
        (field (name "MANUFACTURER") "Panasonic")
        (field (name "MANUFACTURER PART NUMBER") "ERJ3EKF1001V")
      )
      (libsource (lib "Passive") (part "RES 0603 1k 1%"))
    )
    (comp (ref "R13")
      (value "1k")
      (footprint "RES SMD 0603")
      (description "Res Thick Film 0603 1K Ohm 1% 1/10W ±100ppm/°C Molded SMD Punched Carrier T/R")
      (fields
        (field (name "MANUFACTURER") "Panasonic")
        (field (name "MANUFACTURER PART NUMBER") "ERJ3EKF1001V")
      )
      (libsource (lib "Passive") (part "RES 0603 1k 1%"))
    )
    (comp (ref "R14")
      (value "1k")
      (footprint "RES SMD 0603")
      (description "Res Thick Film 0603 1K Ohm 1% 1/10W ±100ppm/°C Molded SMD Punched Carrier T/R")
      (fields
        (field (name "MANUFACTURER") "Panasonic")
        (field (name "MANUFACTURER PART NUMBER") "ERJ3EKF1001V")
      )
      (libsource (lib "Passive") (part "RES 0603 1k 1%"))
    )
    (comp (ref "R15")
      (value "75k")
      (footprint "RES SMD 0603")
      (description "Res Thick Film 0603 75K Ohm 1% 0.1W(1/10W) ±100ppm/C Pad SMD Automotive T/R")
      (fields
        (field (name "MANUFACTURER") "Panasonic")
        (field (name "MANUFACTURER PART NUMBER") "ERJ3RBD7502V")
      )
      (libsource (lib "Passive") (part "RES 0603 75k 1%"))
    )
    (comp (ref "R16")
      (value "12K")
      (footprint "RES SMD 0603")
      (fields
        (field (name "MANUFACTURER") "Yageo")
        (field (name "MANUFACTURER PART NUMBER") "RC0603FR-0712KL")
        (field (name "TOLERANCE") "1%")
      )
      (libsource (lib "Passive") (part "RES 0603 12K 1%"))
    )
    (comp (ref "R17")
      (value "33k")
      (footprint "RES SMD 0603")
      (fields
        (field (name "MANUFACTURER") "Uniroyal")
        (field (name "MANUFACTURER PART NUMBER") "0603WAF3902T5E")
      )
      (libsource (lib "Passive") (part "RES 0603 39k 1%"))
    )
    (comp (ref "R18")
      (value "75k")
      (footprint "RES SMD 0603")
      (description "Res Thick Film 0603 75K Ohm 1% 0.1W(1/10W) ±100ppm/C Pad SMD Automotive T/R")
      (fields
        (field (name "MANUFACTURER") "Panasonic")
        (field (name "MANUFACTURER PART NUMBER") "ERJ3RBD7502V")
      )
      (libsource (lib "Passive") (part "RES 0603 75k 1%"))
    )
    (comp (ref "R19")
      (value "1k")
      (footprint "RES SMD 0603")
      (description "Res Thick Film 0603 1K Ohm 1% 1/10W ±100ppm/°C Molded SMD Punched Carrier T/R")
      (fields
        (field (name "MANUFACTURER") "Panasonic")
        (field (name "MANUFACTURER PART NUMBER") "ERJ3EKF1001V")
      )
      (libsource (lib "Passive") (part "RES 0603 1k 1%"))
    )
    (comp (ref "R20")
      (value "1k")
      (footprint "RES SMD 0603")
      (description "Res Thick Film 0603 1K Ohm 1% 1/10W ±100ppm/°C Molded SMD Punched Carrier T/R")
      (fields
        (field (name "MANUFACTURER") "Panasonic")
        (field (name "MANUFACTURER PART NUMBER") "ERJ3EKF1001V")
      )
      (libsource (lib "Passive") (part "RES 0603 1k 1%"))
    )
    (comp (ref "R21")
      (value "31.6K")
      (footprint "RES SMD 0603")
      (description "100mW Thick Film Resistors 75V ±100ppm/℃ ±1% 31.6kΩ 0603 Chip Resistor - Surface Mount ROHS")
      (fields (field (name "RESISTANCE") "31.6K"))
      (libsource (lib "Passive") (part "RES 0603 31.6k 1%"))
    )
    (comp (ref "R22")
      (value "3.83K")
      (footprint "RES SMD 0603")
      (description "100mW Thick Film Resistors 75V ±100ppm/℃ ±1% 3.83kΩ 0603 Chip Resistor - Surface Mount ROHS")
      (fields (field (name "RESISTANCE") "3.83K"))
      (libsource (lib "Passive") (part "RES 0603 3.83k 1%"))
    )
    (comp (ref "R23")
      (value "10k")
      (footprint "RES SMD 0603")
      (description "100mW Thick Film Resistors 75V ±100ppm/℃ ±1% 10kΩ 0603 Chip Resistor - Surface Mount ROHS")
      (fields
        (field (name "MANUFACTURER") "YAGEO")
        (field (name "MANUFACTURER PART NUMBER") "RC0603FR-0710KL")
      )
      (libsource (lib "Passive") (part "RES 0603 10k 1%"))
    )
    (comp (ref "R24")
      (value "590R")
      (footprint "RES SMD 0603")
      (description "100mW Thick Film Resistors 75V ±100ppm/℃ ±1% 590Ω 0603 Chip Resistor - Surface Mount ROHS")
      (fields
        (field (name "MANUFACTURER") "FOJAN")
        (field (name "MANUFACTURER PART NUMBER") "FRC0603F5900TS")
        (field (name "RESISTANCE") "590R")
      )
      (libsource (lib "Passive") (part "RES 0603 590R 1%"))
    )
    (comp (ref "R25")
      (value "430K")
      (footprint "RES SMD 0805")
      (description "125mW Thick Film Resistors 150V ±100ppm/℃ ±1% 430kΩ 0805 Chip Resistor - Surface Mount ROHS")
      (fields
        (field (name "MANUFACTURER PART NUMBER") "FRC0805F4303TS")
        (field (name "MANUFACTURER") "FOJAN")
        (field (name "RESISTANCE") "430K")
      )
      (libsource (lib "Passive") (part "RES 0805 430k 1%"))
    )
    (comp (ref "R26")
      (value "20K")
      (footprint "RES SMD 0603")
      (description "100mW Thick Film Resistors 75V ±100ppm/℃ ±1% 20kΩ 0603 Chip Resistor - Surface Mount ROHS")
      (fields
        (field (name "MANUFACTURER") "Yageo")
        (field (name "MANUFACTURER PART NUMBER") "RC0603FR-0720KL")
      )
      (libsource (lib "Passive") (part "RES 0603 20K 1%"))
    )
    (comp (ref "R27")
      (value "511R")
      (footprint "RES SMD 0603")
      (description "100mW Thin Film Resistor ±50ppm/℃ ±0.1% 511Ω 0603 Chip Resistor - Surface Mount ROHS")
      (fields (field (name "RESISTANCE") "511R"))
      (libsource (lib "Passive") (part "RES 0603 511R 0.1%"))
    )
    (comp (ref "U1")
      (value "TPS54561DPRR")
      (footprint "TPS54561DPRR")
      (description "4.5V to 60V Input 5A Step-Down DC-DC Converter With Soft-Start and Eco-mode 10-WSON -40 to 125")
      (fields (field (name "MANUFACTURER") "Texas Instruments"))
      (libsource (lib "PMIC") (part "TPS54561DPRR"))
    )
    (comp (ref "U2")
      (value "TPS54561DPRR")
      (footprint "TPS54561DPRR")
      (description "4.5V to 60V Input 5A Step-Down DC-DC Converter With Soft-Start and Eco-mode 10-WSON -40 to 125")
      (fields (field (name "MANUFACTURER") "Texas Instruments"))
      (libsource (lib "PMIC") (part "TPS54561DPRR"))
    )
    (comp (ref "U3")
      (value "TPS54561DPRR")
      (footprint "TPS54561DPRR")
      (description "4.5V to 60V Input 5A Step-Down DC-DC Converter With Soft-Start and Eco-mode 10-WSON -40 to 125")
      (fields (field (name "MANUFACTURER") "Texas Instruments"))
      (libsource (lib "PMIC") (part "TPS54561DPRR"))
    )
    (comp (ref "U4")
      (value "TPS40170RGYR")
      (footprint "TPS40170RGYR")
      (description "Step-down type 4.5V~60V TQFN-20-EP(3.5x4.5) DC-DC Converters ROHS")
      (fields (field (name "MANUFACTURER") "Texas Instruments"))
      (libsource (lib "PMIC") (part "TPS40170RGYR"))
    )
    (comp (ref "U5")
      (value "BA7807FP-E2")
      (footprint "BA7807FP-E2")
      (description "1A 69dB@(120Hz) Fixed 7V Positive electrode 22V TO-252-3 Linear Voltage Regulators (LDO) ROHS")
      (fields (field (name "MANUFACTURER") "ROHM Semicon"))
      (libsource (lib "PMIC") (part "BA7807FP-E2"))
    )
    (comp (ref "U9")
      (value "AMS1117")
      (footprint "Linear reagulator SMD AMS1117 - duplicate")
      (fields
        (field (name "MANUFACTURER") "Advanced Monolithic Systems")
        (field (name "VOLTAGE OUTPUT") "3.3V")
      )
      (libsource (lib "Linear regulator") (part "AMS1117"))
    )
    (comp (ref "VT1")
      (value "SL15N65CD")
      (footprint "TO252")
      (description "650V 15A 83W 205mΩ 205V TO-252 MOSFETs ROHS")
      (fields (field (name "MANUFACTURER") "Sikor"))
      (libsource (lib "Miscellaneous Transistor") (part "SL15N65CD"))
    )
    (comp (ref "VT2")
      (value "SL15N65CD")
      (footprint "TO252")
      (description "650V 15A 83W 205mΩ 205V TO-252 MOSFETs ROHS")
      (fields (field (name "MANUFACTURER") "Sikor"))
      (libsource (lib "Miscellaneous Transistor") (part "SL15N65CD"))
    )
  )
  (nets
    (net (code "1") (name "+3V3") (class "Default")
      (node (ref "C29") (pin "1") (pinfunction "1_1") (pintype "passive"))
      (node (ref "C30") (pin "1") (pinfunction "1_1") (pintype "passive"))
      (node (ref "C37") (pin "1") (pinfunction "1_1") (pintype "passive"))
      (node (ref "C38") (pin "1") (pinfunction "1_1") (pintype "passive"))
      (node (ref "P2") (pin "1") (pinfunction "1_1") (pintype "power_in"))
      (node (ref "P2") (pin "2") (pinfunction "2_2") (pintype "power_in"))
      (node (ref "P2") (pin "3") (pinfunction "3_3") (pintype "power_in"))
      (node (ref "P2") (pin "4") (pinfunction "4_4") (pintype "power_in"))
      (node (ref "P2") (pin "5") (pinfunction "5_5") (pintype "power_in"))
      (node (ref "R10") (pin "2") (pinfunction "2_2") (pintype "passive"))
      (node (ref "U4") (pin "10") (pinfunction "VDD_10") (pintype "passive"))
      (node (ref "U4") (pin "20") (pinfunction "UVLO_20") (pintype "passive"))
      (node (ref "U9") (pin "2") (pinfunction "OUT_2") (pintype "passive"))
    )
    (net (code "2") (name "+5V") (class "Default")
      (node (ref "C2") (pin "1") (pinfunction "1_1") (pintype "passive"))
      (node (ref "C27") (pin "1") (pinfunction "1_1") (pintype "passive"))
      (node (ref "C28") (pin "1") (pinfunction "1_1") (pintype "passive"))
      (node (ref "C3") (pin "1") (pinfunction "1_1") (pintype "passive"))
      (node (ref "C31") (pin "1") (pinfunction "1_1") (pintype "passive"))
      (node (ref "J1") (pin "1") (pinfunction "VCC_1") (pintype "passive"))
      (node (ref "L1") (pin "1") (pinfunction "1_1") (pintype "passive"))
      (node (ref "P3") (pin "1") (pinfunction "1_1") (pintype "power_in"))
      (node (ref "P3") (pin "2") (pinfunction "2_2") (pintype "power_in"))
      (node (ref "P3") (pin "3") (pinfunction "3_3") (pintype "power_in"))
      (node (ref "P3") (pin "4") (pinfunction "4_4") (pintype "power_in"))
      (node (ref "P3") (pin "5") (pinfunction "5_5") (pintype "power_in"))
      (node (ref "R1") (pin "2") (pinfunction "2_2") (pintype "passive"))
      (node (ref "R20") (pin "2") (pinfunction "2_2") (pintype "passive"))
      (node (ref "U9") (pin "3") (pinfunction "IN_3") (pintype "passive"))
    )
    (net (code "3") (name "+6V") (class "Default")
      (node (ref "C16") (pin "1") (pinfunction "1_1") (pintype "passive"))
      (node (ref "C17") (pin "1") (pinfunction "1_1") (pintype "passive"))
      (node (ref "J3") (pin "2") (pinfunction "2_2") (pintype "passive"))
      (node (ref "J4") (pin "2") (pinfunction "2_2") (pintype "passive"))
      (node (ref "J5") (pin "2") (pinfunction "2_2") (pintype "passive"))
      (node (ref "J6") (pin "2") (pinfunction "2_2") (pintype "passive"))
      (node (ref "J7") (pin "2") (pinfunction "2_2") (pintype "passive"))
      (node (ref "L4") (pin "1") (pinfunction "1_1") (pintype "passive"))
      (node (ref "R15") (pin "2") (pinfunction "2_2") (pintype "passive"))
      (node (ref "R19") (pin "2") (pinfunction "2_2") (pintype "passive"))
    )
    (net (code "4") (name "+7V") (class "Default")
      (node (ref "C52") (pin "1") (pinfunction "1_1") (pintype "passive"))
      (node (ref "C53") (pin "1") (pinfunction "1_1") (pintype "passive"))
      (node (ref "J8") (pin "1") (pinfunction "1_1") (pintype "power_in"))
      (node (ref "R14") (pin "2") (pinfunction "2_2") (pintype "passive"))
      (node (ref "U5") (pin "3") (pinfunction "OUT_3") (pintype "passive"))
    )
    (net (code "5") (name "+12") (class "Default")
      (node (ref "C50") (pin "1") (pinfunction "1_1") (pintype "passive"))
      (node (ref "C51") (pin "1") (pinfunction "1_1") (pintype "passive"))
      (node (ref "J12") (pin "1") (pinfunction "1_1") (pintype "power_in"))
      (node (ref "MH5") (pin "1") (pinfunction "1_1") (pintype "passive"))
      (node (ref "MH6") (pin "1") (pinfunction "1_1") (pintype "passive"))
      (node (ref "R13") (pin "2") (pinfunction "2_2") (pintype "passive"))
      (node (ref "U5") (pin "1") (pinfunction "IN_1") (pintype "passive"))
    )
    (net (code "6") (name "+21V") (class "Default")
      (node (ref "C41") (pin "1") (pinfunction "1_1") (pintype "passive"))
      (node (ref "C42") (pin "1") (pinfunction "1_1") (pintype "passive"))
      (node (ref "C43") (pin "1") (pinfunction "1_1") (pintype "passive"))
      (node (ref "C44") (pin "1") (pinfunction "1_1") (pintype "passive"))
      (node (ref "J9") (pin "1") (pinfunction "+_1") (pintype "passive"))
      (node (ref "L3") (pin "1") (pinfunction "1_1") (pintype "passive"))
      (node (ref "R26") (pin "2") (pinfunction "2_2") (pintype "passive"))
      (node (ref "R27") (pin "2") (pinfunction "2_2") (pintype "passive"))
      (node (ref "R9") (pin "2") (pinfunction "2_2") (pintype "passive"))
    )
    (net (code "7") (name "+24V") (class "Default")
      (node (ref "C11") (pin "1") (pinfunction "1_1") (pintype "passive"))
      (node (ref "C12") (pin "1") (pinfunction "1_1") (pintype "passive"))
      (node (ref "J11") (pin "1") (pinfunction "1_1") (pintype "power_in"))
      (node (ref "L2") (pin "1") (pinfunction "1_1") (pintype "passive"))
      (node (ref "R12") (pin "2") (pinfunction "2_2") (pintype "passive"))
      (node (ref "R5") (pin "2") (pinfunction "2_2") (pintype "passive"))
    )
    (net (code "8") (name "+50V") (class "Default")
      (node (ref "C13") (pin "1") (pinfunction "1_1") (pintype "passive"))
      (node (ref "C18") (pin "1") (pinfunction "1_1") (pintype "passive"))
      (node (ref "C24") (pin "1") (pinfunction "1_1") (pintype "passive"))
      (node (ref "C25") (pin "1") (pinfunction "1_1") (pintype "passive"))
      (node (ref "C26") (pin "1") (pinfunction "1_1") (pintype "passive"))
      (node (ref "C32") (pin "1") (pinfunction "1_1") (pintype "passive"))
      (node (ref "C33") (pin "1") (pinfunction "1_1") (pintype "passive"))
      (node (ref "C34") (pin "1") (pinfunction "1_1") (pintype "passive"))
      (node (ref "C35") (pin "1") (pinfunction "1_1") (pintype "passive"))
      (node (ref "C36") (pin "1") (pinfunction "1_1") (pintype "passive"))
      (node (ref "C4") (pin "1") (pinfunction "1_1") (pintype "passive"))
      (node (ref "C8") (pin "1") (pinfunction "1_1") (pintype "passive"))
      (node (ref "C9") (pin "1") (pinfunction "1_1") (pintype "passive"))
      (node (ref "J2") (pin "1") (pinfunction "+_1") (pintype "passive"))
      (node (ref "R11") (pin "2") (pinfunction "2_2") (pintype "passive"))
      (node (ref "U1") (pin "2") (pinfunction "VIN_2") (pintype "power_in"))
      (node (ref "U2") (pin "2") (pinfunction "VIN_2") (pintype "power_in"))
      (node (ref "U3") (pin "2") (pinfunction "VIN_2") (pintype "power_in"))
      (node (ref "U4") (pin "1") (pinfunction "EN_1") (pintype "passive"))
      (node (ref "U4") (pin "19") (pinfunction "VIN_19") (pintype "passive"))
      (node (ref "U4") (pin "3") (pinfunction "M/S_3") (pintype "passive"))
      (node (ref "VT1") (pin "2") (pinfunction "D_2") (pintype "passive"))
    )
    (net (code "9") (name "/Servo1") (class "Default")
      (node (ref "J3") (pin "1") (pinfunction "1_1") (pintype "passive"))
      (node (ref "P1") (pin "5") (pinfunction "5_5") (pintype "passive"))
    )
    (net (code "10") (name "/Servo2") (class "Default")
      (node (ref "J4") (pin "1") (pinfunction "1_1") (pintype "passive"))
      (node (ref "P1") (pin "4") (pinfunction "4_4") (pintype "passive"))
    )
    (net (code "11") (name "/Servo3") (class "Default")
      (node (ref "J5") (pin "1") (pinfunction "1_1") (pintype "passive"))
      (node (ref "P1") (pin "3") (pinfunction "3_3") (pintype "passive"))
    )
    (net (code "12") (name "/Servo4") (class "Default")
      (node (ref "J6") (pin "1") (pinfunction "1_1") (pintype "passive"))
      (node (ref "P1") (pin "2") (pinfunction "2_2") (pintype "passive"))
    )
    (net (code "13") (name "/Servo5") (class "Default")
      (node (ref "J7") (pin "1") (pinfunction "1_1") (pintype "passive"))
      (node (ref "P1") (pin "1") (pinfunction "1_1") (pintype "passive"))
    )
    (net (code "14") (name "GND") (class "Default")
      (node (ref "C11") (pin "2") (pinfunction "2_2") (pintype "passive"))
      (node (ref "C12") (pin "2") (pinfunction "2_2") (pintype "passive"))
      (node (ref "C13") (pin "2") (pinfunction "2_2") (pintype "passive"))
      (node (ref "C14") (pin "2") (pinfunction "2_2") (pintype "passive"))
      (node (ref "C16") (pin "2") (pinfunction "2_2") (pintype "passive"))
      (node (ref "C17") (pin "2") (pinfunction "2_2") (pintype "passive"))
      (node (ref "C18") (pin "2") (pinfunction "2_2") (pintype "passive"))
      (node (ref "C19") (pin "2") (pinfunction "2_2") (pintype "passive"))
      (node (ref "C2") (pin "2") (pinfunction "2_2") (pintype "passive"))
      (node (ref "C20") (pin "2") (pinfunction "2_2") (pintype "passive"))
      (node (ref "C21") (pin "2") (pinfunction "2_2") (pintype "passive"))
      (node (ref "C22") (pin "2") (pinfunction "2_2") (pintype "passive"))
      (node (ref "C23") (pin "2") (pinfunction "2_2") (pintype "passive"))
      (node (ref "C24") (pin "2") (pinfunction "2_2") (pintype "passive"))
      (node (ref "C25") (pin "2") (pinfunction "2_2") (pintype "passive"))
      (node (ref "C26") (pin "2") (pinfunction "2_2") (pintype "passive"))
      (node (ref "C27") (pin "2") (pinfunction "2_2") (pintype "passive"))
      (node (ref "C28") (pin "2") (pinfunction "2_2") (pintype "passive"))
      (node (ref "C29") (pin "2") (pinfunction "2_2") (pintype "passive"))
      (node (ref "C3") (pin "2") (pinfunction "2_2") (pintype "passive"))
      (node (ref "C30") (pin "2") (pinfunction "2_2") (pintype "passive"))
      (node (ref "C31") (pin "2") (pinfunction "2_2") (pintype "passive"))
      (node (ref "C32") (pin "2") (pinfunction "2_2") (pintype "passive"))
      (node (ref "C33") (pin "2") (pinfunction "2_2") (pintype "passive"))
      (node (ref "C34") (pin "2") (pinfunction "2_2") (pintype "passive"))
      (node (ref "C35") (pin "2") (pinfunction "2_2") (pintype "passive"))
      (node (ref "C36") (pin "2") (pinfunction "2_2") (pintype "passive"))
      (node (ref "C37") (pin "2") (pinfunction "2_2") (pintype "passive"))
      (node (ref "C38") (pin "2") (pinfunction "2_2") (pintype "passive"))
      (node (ref "C4") (pin "2") (pinfunction "2_2") (pintype "passive"))
      (node (ref "C40") (pin "2") (pinfunction "2_2") (pintype "passive"))
      (node (ref "C41") (pin "2") (pinfunction "2_2") (pintype "passive"))
      (node (ref "C42") (pin "2") (pinfunction "2_2") (pintype "passive"))
      (node (ref "C43") (pin "2") (pinfunction "2_2") (pintype "passive"))
      (node (ref "C44") (pin "2") (pinfunction "2_2") (pintype "passive"))
      (node (ref "C47") (pin "2") (pinfunction "2_2") (pintype "passive"))
      (node (ref "C48") (pin "2") (pinfunction "2_2") (pintype "passive"))
      (node (ref "C5") (pin "2") (pinfunction "2_2") (pintype "passive"))
      (node (ref "C50") (pin "2") (pinfunction "2_2") (pintype "passive"))
      (node (ref "C51") (pin "2") (pinfunction "2_2") (pintype "passive"))
      (node (ref "C52") (pin "2") (pinfunction "2_2") (pintype "passive"))
      (node (ref "C53") (pin "2") (pinfunction "2_2") (pintype "passive"))
      (node (ref "C6") (pin "2") (pinfunction "2_2") (pintype "passive"))
      (node (ref "C7") (pin "2") (pinfunction "2_2") (pintype "passive"))
      (node (ref "C8") (pin "2") (pinfunction "2_2") (pintype "passive"))
      (node (ref "C9") (pin "2") (pinfunction "2_2") (pintype "passive"))
      (node (ref "D1") (pin "A") (pinfunction "A_A") (pintype "passive"))
      (node (ref "D12") (pin "2") (pinfunction "2_2") (pintype "passive"))
      (node (ref "D13") (pin "2") (pinfunction "2_2") (pintype "passive"))
      (node (ref "D2") (pin "A") (pinfunction "A_A") (pintype "passive"))
      (node (ref "D3") (pin "2") (pinfunction "2_2") (pintype "passive"))
      (node (ref "D4") (pin "2") (pinfunction "2_2") (pintype "passive"))
      (node (ref "D5") (pin "2") (pinfunction "2_2") (pintype "passive"))
      (node (ref "D6") (pin "2") (pinfunction "2_2") (pintype "passive"))
      (node (ref "D7") (pin "2") (pinfunction "2_2") (pintype "passive"))
      (node (ref "D8") (pin "A") (pinfunction "A_A") (pintype "passive"))
      (node (ref "D9") (pin "2") (pinfunction "2_2") (pintype "passive"))
      (node (ref "J1") (pin "4") (pinfunction "GND_4") (pintype "passive"))
      (node (ref "J11") (pin "2") (pinfunction "2_2") (pintype "power_in"))
      (node (ref "J11") (pin "3") (pinfunction "3_3") (pintype "power_in"))
      (node (ref "J12") (pin "2") (pinfunction "2_2") (pintype "power_in"))
      (node (ref "J12") (pin "3") (pinfunction "3_3") (pintype "power_in"))
      (node (ref "J2") (pin "2") (pinfunction "-_2") (pintype "passive"))
      (node (ref "J3") (pin "3") (pinfunction "3_3") (pintype "passive"))
      (node (ref "J4") (pin "3") (pinfunction "3_3") (pintype "passive"))
      (node (ref "J5") (pin "3") (pinfunction "3_3") (pintype "passive"))
      (node (ref "J6") (pin "3") (pinfunction "3_3") (pintype "passive"))
      (node (ref "J7") (pin "3") (pinfunction "3_3") (pintype "passive"))
      (node (ref "J8") (pin "2") (pinfunction "2_2") (pintype "power_in"))
      (node (ref "J8") (pin "3") (pinfunction "3_3") (pintype "power_in"))
      (node (ref "J9") (pin "2") (pinfunction "-_2") (pintype "passive"))
      (node (ref "MH7") (pin "1") (pinfunction "1_1") (pintype "passive"))
      (node (ref "MH8") (pin "1") (pinfunction "1_1") (pintype "passive"))
      (node (ref "P2") (pin "10") (pinfunction "10_10") (pintype "power_in"))
      (node (ref "P2") (pin "6") (pinfunction "6_6") (pintype "power_in"))
      (node (ref "P2") (pin "7") (pinfunction "7_7") (pintype "power_in"))
      (node (ref "P2") (pin "8") (pinfunction "8_8") (pintype "power_in"))
      (node (ref "P2") (pin "9") (pinfunction "9_9") (pintype "power_in"))
      (node (ref "P3") (pin "10") (pinfunction "10_10") (pintype "power_in"))
      (node (ref "P3") (pin "6") (pinfunction "6_6") (pintype "power_in"))
      (node (ref "P3") (pin "7") (pinfunction "7_7") (pintype "power_in"))
      (node (ref "P3") (pin "8") (pinfunction "8_8") (pintype "power_in"))
      (node (ref "P3") (pin "9") (pinfunction "9_9") (pintype "power_in"))
      (node (ref "R16") (pin "1") (pinfunction "1_1") (pintype "passive"))
      (node (ref "R18") (pin "1") (pinfunction "1_1") (pintype "passive"))
      (node (ref "R2") (pin "1") (pinfunction "1_1") (pintype "passive"))
      (node (ref "R21") (pin "1") (pinfunction "1_1") (pintype "passive"))
      (node (ref "R23") (pin "1") (pinfunction "1_1") (pintype "passive"))
      (node (ref "R24") (pin "1") (pinfunction "1_1") (pintype "passive"))
      (node (ref "R25") (pin "1") (pinfunction "1_1") (pintype "passive"))
      (node (ref "R4") (pin "1") (pinfunction "1_1") (pintype "passive"))
      (node (ref "R6") (pin "1") (pinfunction "1_1") (pintype "passive"))
      (node (ref "R8") (pin "1") (pinfunction "1_1") (pintype "passive"))
      (node (ref "U1") (pin "11") (pinfunction "TP_11") (pintype "power_in"))
      (node (ref "U1") (pin "8") (pinfunction "GND_8") (pintype "power_in"))
      (node (ref "U2") (pin "11") (pinfunction "TP_11") (pintype "power_in"))
      (node (ref "U2") (pin "8") (pinfunction "GND_8") (pintype "power_in"))
      (node (ref "U3") (pin "11") (pinfunction "TP_11") (pintype "power_in"))
      (node (ref "U3") (pin "8") (pinfunction "GND_8") (pintype "power_in"))
      (node (ref "U4") (pin "13") (pinfunction "PGND_13") (pintype "passive"))
      (node (ref "U4") (pin "21") (pinfunction "GND_21") (pintype "passive"))
      (node (ref "U4") (pin "9") (pinfunction "AGND_9") (pintype "passive"))
      (node (ref "U5") (pin "2") (pinfunction "GND_2") (pintype "passive"))
      (node (ref "U9") (pin "1") (pinfunction "GND_1") (pintype "passive"))
      (node (ref "VT2") (pin "3") (pinfunction "S_3") (pintype "passive"))
    )
    (net (code "15") (name "Net-(C7-Pad1)") (class "Default")
      (node (ref "C7") (pin "1") (pinfunction "1_1") (pintype "passive"))
      (node (ref "R3") (pin "1") (pinfunction "1_1") (pintype "passive"))
    )
    (net (code "16") (name "Net-(C21-Pad1)") (class "Default")
      (node (ref "C21") (pin "1") (pinfunction "1_1") (pintype "passive"))
      (node (ref "R17") (pin "1") (pinfunction "1_1") (pintype "passive"))
    )
    (net (code "17") (name "Net-(C23-Pad1)") (class "Default")
      (node (ref "C23") (pin "1") (pinfunction "1_1") (pintype "passive"))
      (node (ref "R7") (pin "1") (pinfunction "1_1") (pintype "passive"))
    )
    (net (code "18") (name "Net-(C45-Pad2)") (class "Default")
      (node (ref "C45") (pin "2") (pinfunction "2_2") (pintype "passive"))
      (node (ref "R22") (pin "2") (pinfunction "2_2") (pintype "passive"))
    )
    (net (code "19") (name "Net-(C49-Pad2)") (class "Default")
      (node (ref "C49") (pin "2") (pinfunction "2_2") (pintype "passive"))
      (node (ref "R27") (pin "1") (pinfunction "1_1") (pintype "passive"))
    )
    (net (code "20") (name "Net-(D3-Pad1)") (class "Default")
      (node (ref "D3") (pin "1") (pinfunction "1_1") (pintype "passive"))
      (node (ref "R9") (pin "1") (pinfunction "1_1") (pintype "passive"))
    )
    (net (code "21") (name "Net-(D4-Pad1)") (class "Default")
      (node (ref "D4") (pin "1") (pinfunction "1_1") (pintype "passive"))
      (node (ref "R11") (pin "1") (pinfunction "1_1") (pintype "passive"))
    )
    (net (code "22") (name "Net-(D5-Pad1)") (class "Default")
      (node (ref "D5") (pin "1") (pinfunction "1_1") (pintype "passive"))
      (node (ref "R12") (pin "1") (pinfunction "1_1") (pintype "passive"))
    )
    (net (code "23") (name "Net-(D6-Pad1)") (class "Default")
      (node (ref "D6") (pin "1") (pinfunction "1_1") (pintype "passive"))
      (node (ref "R13") (pin "1") (pinfunction "1_1") (pintype "passive"))
    )
    (net (code "24") (name "Net-(D7-Pad1)") (class "Default")
      (node (ref "D7") (pin "1") (pinfunction "1_1") (pintype "passive"))
      (node (ref "R14") (pin "1") (pinfunction "1_1") (pintype "passive"))
    )
    (net (code "25") (name "Net-(D9-Pad1)") (class "Default")
      (node (ref "D9") (pin "1") (pinfunction "1_1") (pintype "passive"))
      (node (ref "R10") (pin "1") (pinfunction "1_1") (pintype "passive"))
    )
    (net (code "26") (name "Net-(D12-Pad1)") (class "Default")
      (node (ref "D12") (pin "1") (pinfunction "1_1") (pintype "passive"))
      (node (ref "R19") (pin "1") (pinfunction "1_1") (pintype "passive"))
    )
    (net (code "27") (name "Net-(D13-Pad1)") (class "Default")
      (node (ref "D13") (pin "1") (pinfunction "1_1") (pintype "passive"))
      (node (ref "R20") (pin "1") (pinfunction "1_1") (pintype "passive"))
    )
    (net (code "28") (name "Net-(U1-BOOT)") (class "Default")
      (node (ref "C1") (pin "1") (pinfunction "1_1") (pintype "passive"))
      (node (ref "U1") (pin "1") (pinfunction "BOOT_1") (pintype "output"))
    )
    (net (code "29") (name "Net-(U1-COMP)") (class "Default")
      (node (ref "C6") (pin "1") (pinfunction "1_1") (pintype "passive"))
      (node (ref "R3") (pin "2") (pinfunction "2_2") (pintype "passive"))
      (node (ref "U1") (pin "7") (pinfunction "COMP_7") (pintype "output"))
    )
    (net (code "30") (name "Net-(U1-FB)") (class "Default")
      (node (ref "R1") (pin "1") (pinfunction "1_1") (pintype "passive"))
      (node (ref "R2") (pin "2") (pinfunction "2_2") (pintype "passive"))
      (node (ref "U1") (pin "6") (pinfunction "FB_6") (pintype "input"))
    )
    (net (code "31") (name "Net-(U1-RT{slash}CLK)") (class "Default")
      (node (ref "R4") (pin "2") (pinfunction "2_2") (pintype "passive"))
      (node (ref "U1") (pin "5") (pinfunction "RT/CLK_5") (pintype "input"))
    )
    (net (code "32") (name "Net-(U1-SS{slash}TR)") (class "Default")
      (node (ref "C5") (pin "1") (pinfunction "1_1") (pintype "passive"))
      (node (ref "U1") (pin "4") (pinfunction "SS/TR_4") (pintype "output"))
    )
    (net (code "33") (name "Net-(U1-SW)") (class "Default")
      (node (ref "C1") (pin "2") (pinfunction "2_2") (pintype "passive"))
      (node (ref "D1") (pin "C") (pinfunction "C_C") (pintype "passive"))
      (node (ref "L1") (pin "2") (pinfunction "2_2") (pintype "passive"))
      (node (ref "U1") (pin "9") (pinfunction "SW_9") (pintype "input"))
    )
    (net (code "34") (name "Net-(U2-BOOT)") (class "Default")
      (node (ref "C10") (pin "1") (pinfunction "1_1") (pintype "passive"))
      (node (ref "U2") (pin "1") (pinfunction "BOOT_1") (pintype "output"))
    )
    (net (code "35") (name "Net-(U2-COMP)") (class "Default")
      (node (ref "C22") (pin "1") (pinfunction "1_1") (pintype "passive"))
      (node (ref "R7") (pin "2") (pinfunction "2_2") (pintype "passive"))
      (node (ref "U2") (pin "7") (pinfunction "COMP_7") (pintype "output"))
    )
    (net (code "36") (name "Net-(U2-FB)") (class "Default")
      (node (ref "R5") (pin "1") (pinfunction "1_1") (pintype "passive"))
      (node (ref "R6") (pin "2") (pinfunction "2_2") (pintype "passive"))
      (node (ref "U2") (pin "6") (pinfunction "FB_6") (pintype "input"))
    )
    (net (code "37") (name "Net-(U2-RT{slash}CLK)") (class "Default")
      (node (ref "R8") (pin "2") (pinfunction "2_2") (pintype "passive"))
      (node (ref "U2") (pin "5") (pinfunction "RT/CLK_5") (pintype "input"))
    )
    (net (code "38") (name "Net-(U2-SS{slash}TR)") (class "Default")
      (node (ref "C14") (pin "1") (pinfunction "1_1") (pintype "passive"))
      (node (ref "U2") (pin "4") (pinfunction "SS/TR_4") (pintype "output"))
    )
    (net (code "39") (name "Net-(U2-SW)") (class "Default")
      (node (ref "C10") (pin "2") (pinfunction "2_2") (pintype "passive"))
      (node (ref "D2") (pin "C") (pinfunction "C_C") (pintype "passive"))
      (node (ref "L2") (pin "2") (pinfunction "2_2") (pintype "passive"))
      (node (ref "U2") (pin "9") (pinfunction "SW_9") (pintype "input"))
    )
    (net (code "40") (name "Net-(U3-BOOT)") (class "Default")
      (node (ref "C15") (pin "1") (pinfunction "1_1") (pintype "passive"))
      (node (ref "U3") (pin "1") (pinfunction "BOOT_1") (pintype "output"))
    )
    (net (code "41") (name "Net-(U3-COMP)") (class "Default")
      (node (ref "C20") (pin "1") (pinfunction "1_1") (pintype "passive"))
      (node (ref "R17") (pin "2") (pinfunction "2_2") (pintype "passive"))
      (node (ref "U3") (pin "7") (pinfunction "COMP_7") (pintype "output"))
    )
    (net (code "42") (name "Net-(U3-FB)") (class "Default")
      (node (ref "R15") (pin "1") (pinfunction "1_1") (pintype "passive"))
      (node (ref "R16") (pin "2") (pinfunction "2_2") (pintype "passive"))
      (node (ref "U3") (pin "6") (pinfunction "FB_6") (pintype "input"))
    )
    (net (code "43") (name "Net-(U3-RT{slash}CLK)") (class "Default")
      (node (ref "R18") (pin "2") (pinfunction "2_2") (pintype "passive"))
      (node (ref "U3") (pin "5") (pinfunction "RT/CLK_5") (pintype "input"))
    )
    (net (code "44") (name "Net-(U3-SS{slash}TR)") (class "Default")
      (node (ref "C19") (pin "1") (pinfunction "1_1") (pintype "passive"))
      (node (ref "U3") (pin "4") (pinfunction "SS/TR_4") (pintype "output"))
    )
    (net (code "45") (name "Net-(U3-SW)") (class "Default")
      (node (ref "C15") (pin "2") (pinfunction "2_2") (pintype "passive"))
      (node (ref "D8") (pin "C") (pinfunction "C_C") (pintype "passive"))
      (node (ref "L4") (pin "2") (pinfunction "2_2") (pintype "passive"))
      (node (ref "U3") (pin "9") (pinfunction "SW_9") (pintype "input"))
    )
    (net (code "46") (name "Net-(U4-BOOT)") (class "Default")
      (node (ref "C39") (pin "1") (pinfunction "1_1") (pintype "passive"))
      (node (ref "U4") (pin "18") (pinfunction "BOOT_18") (pintype "passive"))
    )
    (net (code "47") (name "Net-(U4-COMP)") (class "Default")
      (node (ref "C45") (pin "1") (pinfunction "1_1") (pintype "passive"))
      (node (ref "C46") (pin "2") (pinfunction "2_2") (pintype "passive"))
      (node (ref "U4") (pin "8") (pinfunction "COMP_8") (pintype "passive"))
    )
    (net (code "48") (name "Net-(U4-FB)") (class "Default")
      (node (ref "C46") (pin "1") (pinfunction "1_1") (pintype "passive"))
      (node (ref "C49") (pin "1") (pinfunction "1_1") (pintype "passive"))
      (node (ref "R22") (pin "1") (pinfunction "1_1") (pintype "passive"))
      (node (ref "R24") (pin "2") (pinfunction "2_2") (pintype "passive"))
      (node (ref "R26") (pin "1") (pinfunction "1_1") (pintype "passive"))
      (node (ref "U4") (pin "7") (pinfunction "FB_7") (pintype "passive"))
    )
    (net (code "49") (name "Net-(U4-HDRV)") (class "Default")
      (node (ref "U4") (pin "17") (pinfunction "HDRV_17") (pintype "passive"))
      (node (ref "VT1") (pin "1") (pinfunction "G_1") (pintype "passive"))
    )
    (net (code "50") (name "Net-(U4-ILIM)") (class "Default")
      (node (ref "C48") (pin "1") (pinfunction "1_1") (pintype "passive"))
      (node (ref "R25") (pin "2") (pinfunction "2_2") (pintype "passive"))
      (node (ref "U4") (pin "12") (pinfunction "ILIM_12") (pintype "passive"))
    )
    (net (code "51") (name "Net-(U4-LDRV)") (class "Default")
      (node (ref "R23") (pin "2") (pinfunction "2_2") (pintype "passive"))
      (node (ref "U4") (pin "14") (pinfunction "LDRV_14") (pintype "passive"))
      (node (ref "VT2") (pin "1") (pinfunction "G_1") (pintype "passive"))
    )
    (net (code "52") (name "Net-(U4-RT)") (class "Default")
      (node (ref "R21") (pin "2") (pinfunction "2_2") (pintype "passive"))
      (node (ref "U4") (pin "4") (pinfunction "RT_4") (pintype "passive"))
    )
    (net (code "53") (name "Net-(U4-SS)") (class "Default")
      (node (ref "C40") (pin "1") (pinfunction "1_1") (pintype "passive"))
      (node (ref "U4") (pin "5") (pinfunction "SS_5") (pintype "passive"))
    )
    (net (code "54") (name "Net-(U4-SW)") (class "Default")
      (node (ref "C39") (pin "2") (pinfunction "2_2") (pintype "passive"))
      (node (ref "L3") (pin "2") (pinfunction "2_2") (pintype "passive"))
      (node (ref "U4") (pin "16") (pinfunction "SW_16") (pintype "passive"))
      (node (ref "VT1") (pin "3") (pinfunction "S_3") (pintype "passive"))
      (node (ref "VT2") (pin "2") (pinfunction "D_2") (pintype "passive"))
    )
    (net (code "55") (name "Net-(U4-VBP)") (class "Default")
      (node (ref "C47") (pin "1") (pinfunction "1_1") (pintype "passive"))
      (node (ref "U4") (pin "15") (pinfunction "VBP_15") (pintype "passive"))
    )
    (net (code "56") (name "unconnected-(J1-D+-Pad3)") (class "Default")
      (node (ref "J1") (pin "3") (pinfunction "D+_3") (pintype "passive"))
    )
    (net (code "57") (name "unconnected-(J1-D--Pad2)") (class "Default")
      (node (ref "J1") (pin "2") (pinfunction "D-_2") (pintype "passive"))
    )
    (net (code "58") (name "unconnected-(MH1-Pad1)") (class "Default")
      (node (ref "MH1") (pin "1") (pinfunction "1_1") (pintype "passive+no_connect"))
    )
    (net (code "59") (name "unconnected-(MH2-Pad1)") (class "Default")
      (node (ref "MH2") (pin "1") (pinfunction "1_1") (pintype "passive+no_connect"))
    )
    (net (code "60") (name "unconnected-(MH3-Pad1)") (class "Default")
      (node (ref "MH3") (pin "1") (pinfunction "1_1") (pintype "passive+no_connect"))
    )
    (net (code "61") (name "unconnected-(MH4-Pad1)") (class "Default")
      (node (ref "MH4") (pin "1") (pinfunction "1_1") (pintype "passive+no_connect"))
    )
    (net (code "62") (name "unconnected-(U1-EN-Pad3)") (class "Default")
      (node (ref "U1") (pin "3") (pinfunction "EN_3") (pintype "input+no_connect"))
    )
    (net (code "63") (name "unconnected-(U1-PWRGD-Pad10)") (class "Default")
      (node (ref "U1") (pin "10") (pinfunction "PWRGD_10") (pintype "output+no_connect"))
    )
    (net (code "64") (name "unconnected-(U2-EN-Pad3)") (class "Default")
      (node (ref "U2") (pin "3") (pinfunction "EN_3") (pintype "input+no_connect"))
    )
    (net (code "65") (name "unconnected-(U2-PWRGD-Pad10)") (class "Default")
      (node (ref "U2") (pin "10") (pinfunction "PWRGD_10") (pintype "output+no_connect"))
    )
    (net (code "66") (name "unconnected-(U3-EN-Pad3)") (class "Default")
      (node (ref "U3") (pin "3") (pinfunction "EN_3") (pintype "input+no_connect"))
    )
    (net (code "67") (name "unconnected-(U3-PWRGD-Pad10)") (class "Default")
      (node (ref "U3") (pin "10") (pinfunction "PWRGD_10") (pintype "output+no_connect"))
    )
    (net (code "68") (name "unconnected-(U4-PGOOD-Pad11)") (class "Default")
      (node (ref "U4") (pin "11") (pinfunction "PGOOD_11") (pintype "passive+no_connect"))
    )
    (net (code "69") (name "unconnected-(U4-SYNC-Pad2)") (class "Default")
      (node (ref "U4") (pin "2") (pinfunction "SYNC_2") (pintype "passive+no_connect"))
    )
    (net (code "70") (name "unconnected-(U4-TRK-Pad6)") (class "Default")
      (node (ref "U4") (pin "6") (pinfunction "TRK_6") (pintype "passive+no_connect"))
    )
    (net (code "71") (name "unconnected-(U9-OUT-Pad4)") (class "Default")
      (node (ref "U9") (pin "4") (pinfunction "OUT_4") (pintype "passive+no_connect"))
    )
  )
)
